# design.net
KiCad netlist of a schematic drawn in Altium Designer
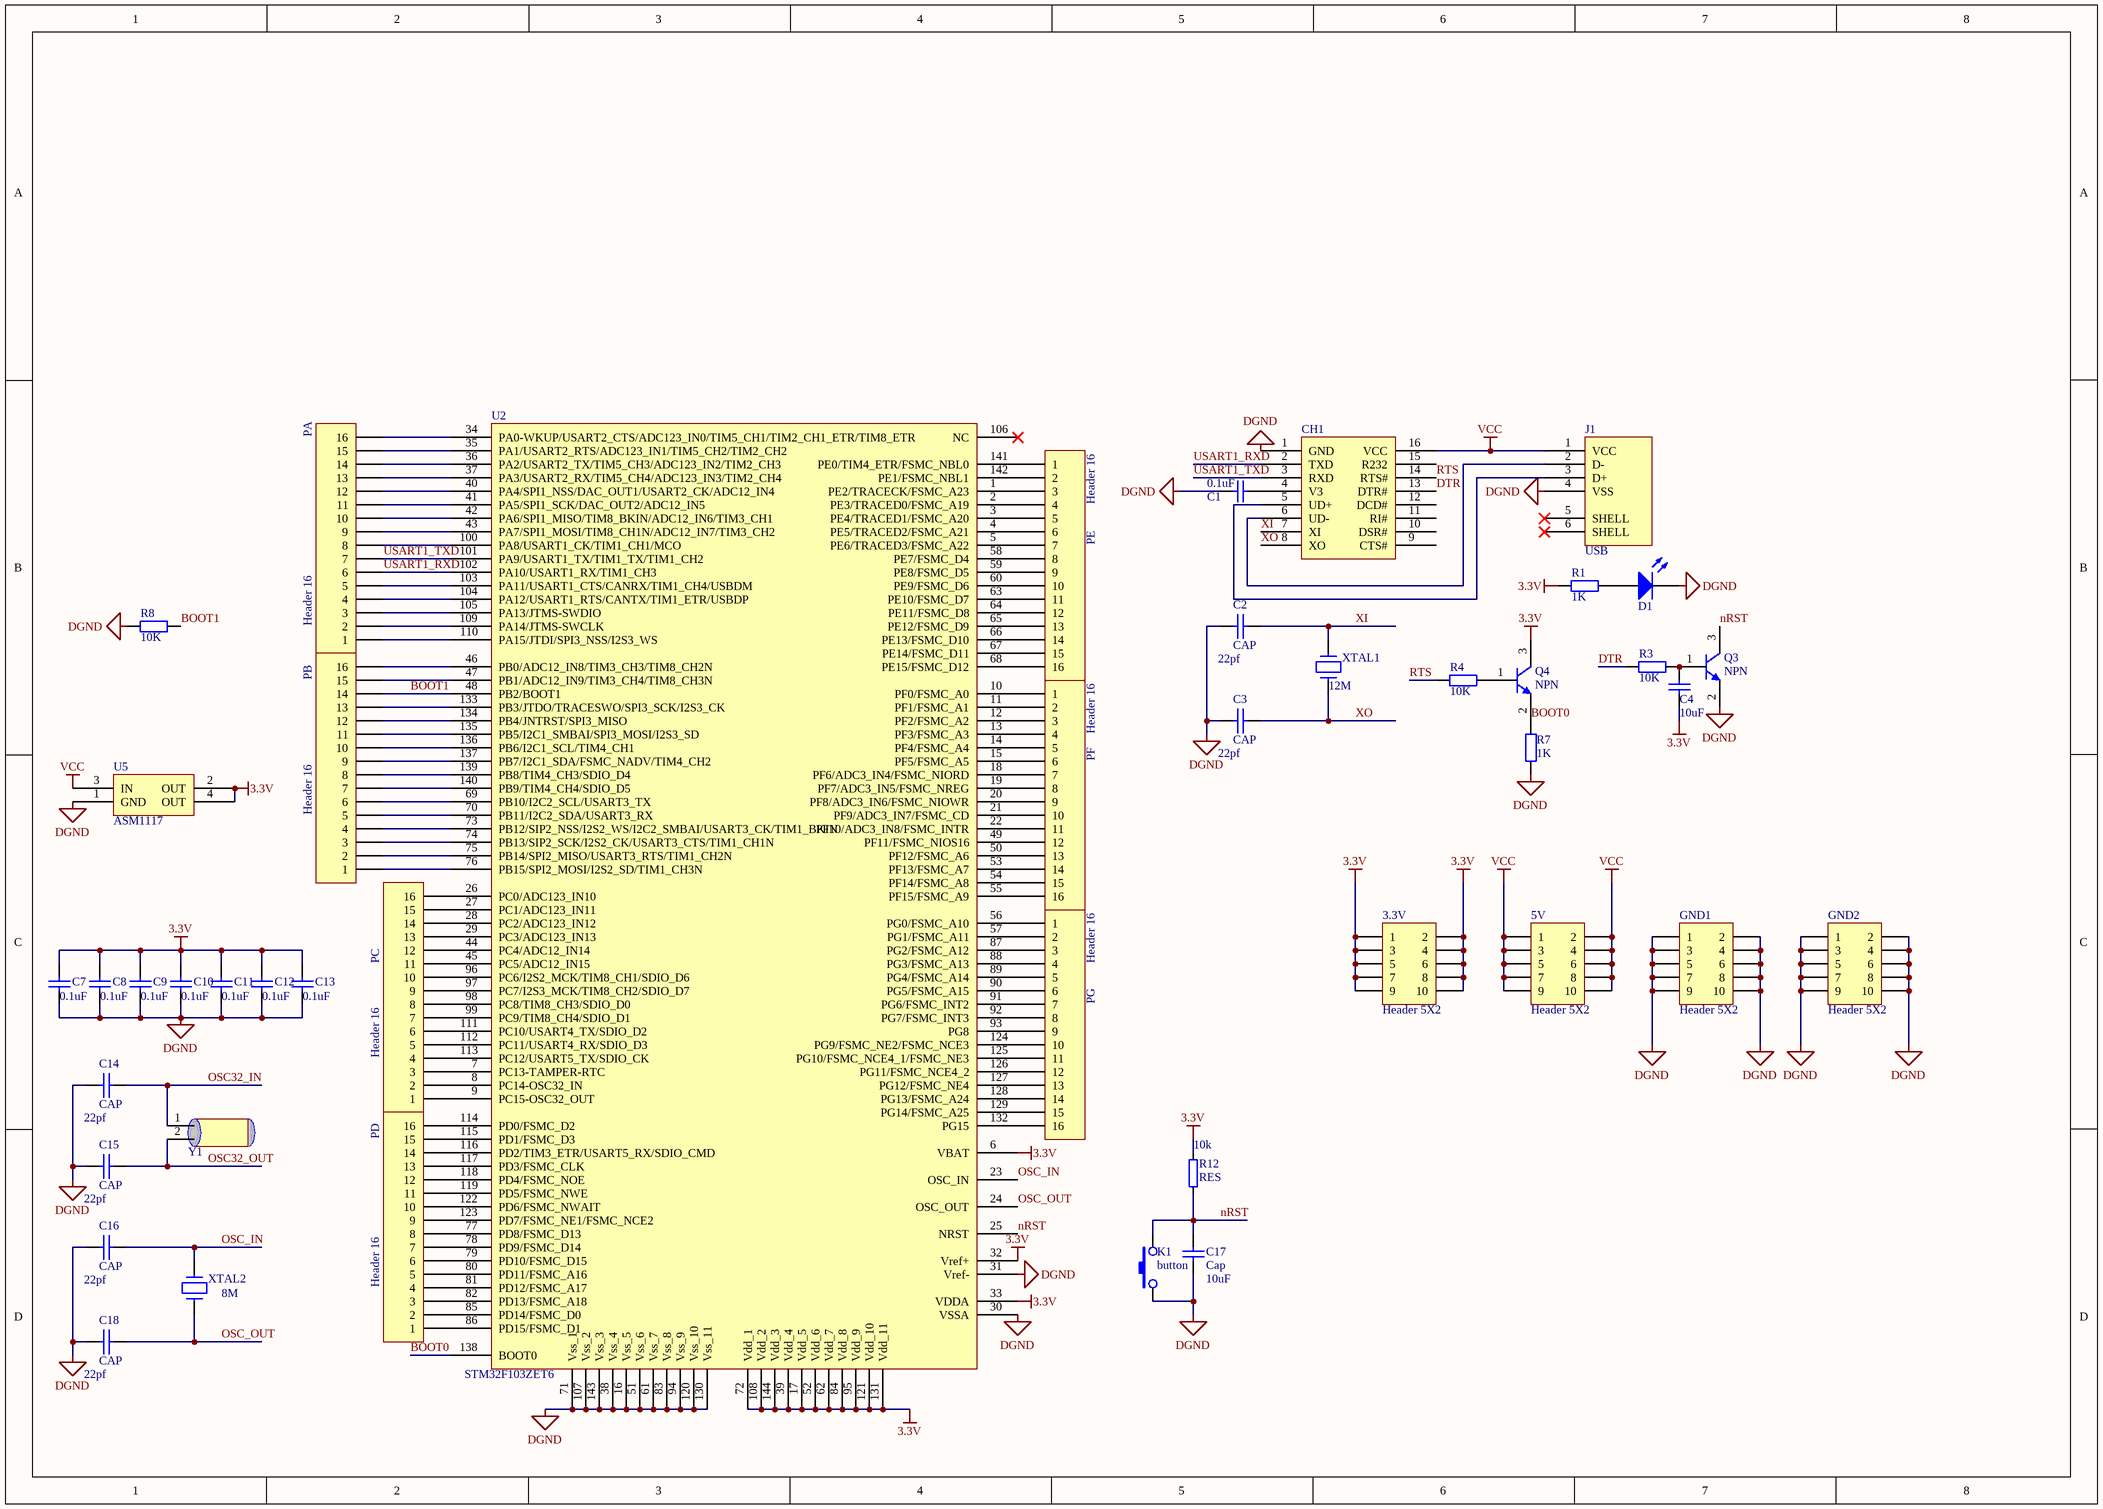
[diagram p0: 最小系统板.SchDoc]

(export (version "E")
  (design (tool "Eeschema 10.0.6"))
  (components
    (comp (ref "3.3V")
      (value "Header 5X2")
      (footprint "HDR2X5")
      (description "Header, 5-Pin, Dual row")
      (fields (field (name "PUBLISHER") "Altium Limited"))
      (libsource (lib "Miscellaneous Connectors") (part "Header 5X2"))
    )
    (comp (ref "5V")
      (value "Header 5X2")
      (footprint "HDR2X5")
      (description "Header, 5-Pin, Dual row")
      (fields (field (name "PUBLISHER") "Altium Limited"))
      (libsource (lib "Miscellaneous Connectors") (part "Header 5X2"))
    )
    (comp (ref "C1")
      (value "0.1uF")
      (footprint "0805")
      (description "Capacitor")
      (fields (field (name "Comment") "Cap") (field (name "PUBLISHER") "Altium Limited"))
      (libsource (lib "Miscellaneous Devices") (part "Cap"))
    )
    (comp (ref "C2")
      (value "CAP")
      (footprint "0805")
      (fields (field (name "ALTIUM_VALUE") "22pf"))
      (libsource (lib "常用元件库") (part "CAP"))
    )
    (comp (ref "C3")
      (value "CAP")
      (footprint "0805")
      (fields (field (name "ALTIUM_VALUE") "22pf"))
      (libsource (lib "常用元件库") (part "CAP"))
    )
    (comp (ref "C4")
      (value "10uF")
      (footprint "1206")
      (description "Capacitor")
      (fields (field (name "Comment") "Cap") (field (name "PUBLISHER") "Altium Limited"))
      (libsource (lib "Miscellaneous Devices") (part "Cap"))
    )
    (comp (ref "C7")
      (value "0.1uF")
      (footprint "0805")
      (description "Capacitor")
      (fields (field (name "Comment") "Cap") (field (name "PUBLISHER") "Altium Limited"))
      (libsource (lib "Miscellaneous Devices") (part "Cap"))
    )
    (comp (ref "C8")
      (value "0.1uF")
      (footprint "0805")
      (description "Capacitor")
      (fields (field (name "Comment") "Cap") (field (name "PUBLISHER") "Altium Limited"))
      (libsource (lib "Miscellaneous Devices") (part "Cap"))
    )
    (comp (ref "C9")
      (value "0.1uF")
      (footprint "0805")
      (description "Capacitor")
      (fields (field (name "Comment") "Cap") (field (name "PUBLISHER") "Altium Limited"))
      (libsource (lib "Miscellaneous Devices") (part "Cap"))
    )
    (comp (ref "C10")
      (value "0.1uF")
      (footprint "0805")
      (description "Capacitor")
      (fields (field (name "Comment") "Cap") (field (name "PUBLISHER") "Altium Limited"))
      (libsource (lib "Miscellaneous Devices") (part "Cap"))
    )
    (comp (ref "C11")
      (value "0.1uF")
      (footprint "0805")
      (description "Capacitor")
      (fields (field (name "Comment") "Cap") (field (name "PUBLISHER") "Altium Limited"))
      (libsource (lib "Miscellaneous Devices") (part "Cap"))
    )
    (comp (ref "C12")
      (value "0.1uF")
      (footprint "0805")
      (description "Capacitor")
      (fields (field (name "Comment") "Cap") (field (name "PUBLISHER") "Altium Limited"))
      (libsource (lib "Miscellaneous Devices") (part "Cap"))
    )
    (comp (ref "C13")
      (value "0.1uF")
      (footprint "0805")
      (description "Capacitor")
      (fields (field (name "Comment") "Cap") (field (name "PUBLISHER") "Altium Limited"))
      (libsource (lib "Miscellaneous Devices") (part "Cap"))
    )
    (comp (ref "C14")
      (value "CAP")
      (footprint "0805")
      (fields (field (name "ALTIUM_VALUE") "22pf"))
      (libsource (lib "常用元件库") (part "CAP"))
    )
    (comp (ref "C15")
      (value "CAP")
      (footprint "0805")
      (fields (field (name "ALTIUM_VALUE") "22pf"))
      (libsource (lib "常用元件库") (part "CAP"))
    )
    (comp (ref "C16")
      (value "CAP")
      (footprint "0805")
      (fields (field (name "ALTIUM_VALUE") "22pf"))
      (libsource (lib "常用元件库") (part "CAP"))
    )
    (comp (ref "C17")
      (value "Cap")
      (footprint "1206")
      (description "Capacitor")
      (fields (field (name "ALTIUM_VALUE") "10uF") (field (name "PUBLISHER") "Altium Limited"))
      (libsource (lib "Miscellaneous Devices") (part "Cap"))
    )
    (comp (ref "C18")
      (value "CAP")
      (footprint "0805")
      (fields (field (name "ALTIUM_VALUE") "22pf"))
      (libsource (lib "常用元件库") (part "CAP"))
    )
    (comp (ref "CH1")
      (value "Component_1")
      (footprint "SOIC127P600X170-16N")
      (libsource (lib "CH340G") (part "Component_1"))
    )
    (comp (ref "D1")
      (value "LED0")
      (footprint "LED-0805")
      (description "发光二极管")
      (fields (field (name "PUBLISHER") "Altium Limited"))
      (libsource (lib "fszhang") (part "LED0"))
    )
    (comp (ref "GND1")
      (value "Header 5X2")
      (footprint "HDR2X5")
      (description "Header, 5-Pin, Dual row")
      (fields (field (name "PUBLISHER") "Altium Limited"))
      (libsource (lib "Miscellaneous Connectors") (part "Header 5X2"))
    )
    (comp (ref "GND2")
      (value "Header 5X2")
      (footprint "HDR2X5")
      (description "Header, 5-Pin, Dual row")
      (fields (field (name "PUBLISHER") "Altium Limited"))
      (libsource (lib "Miscellaneous Connectors") (part "Header 5X2"))
    )
    (comp (ref "J1")
      (value "USB")
      (footprint "USB_B1")
      (description "USB接口")
      (libsource (lib "HDR_fszhang") (part "USB"))
    )
    (comp (ref "K1") (value "button") (footprint "SW_PB4_A1") (libsource (lib "my Library") (part "button")))
    (comp (ref "PA")
      (value "Header 16")
      (footprint "HDR1X16")
      (description "Header, 16-Pin")
      (fields (field (name "PUBLISHER") "Altium Limited"))
      (libsource (lib "") (part "Header 16_1"))
    )
    (comp (ref "PB")
      (value "Header 16")
      (footprint "HDR1X16")
      (description "Header, 16-Pin")
      (fields (field (name "PUBLISHER") "Altium Limited"))
      (libsource (lib "") (part "Header 16_1"))
    )
    (comp (ref "PC")
      (value "Header 16")
      (footprint "HDR1X16")
      (description "Header, 16-Pin")
      (fields (field (name "PUBLISHER") "Altium Limited"))
      (libsource (lib "") (part "Header 16_1"))
    )
    (comp (ref "PD")
      (value "Header 16")
      (footprint "HDR1X16")
      (description "Header, 16-Pin")
      (fields (field (name "PUBLISHER") "Altium Limited"))
      (libsource (lib "") (part "Header 16_1"))
    )
    (comp (ref "PE")
      (value "Header 16")
      (footprint "HDR1X16")
      (description "Header, 16-Pin")
      (fields (field (name "PUBLISHER") "Altium Limited"))
      (libsource (lib "Miscellaneous Connectors") (part "Header 16"))
    )
    (comp (ref "PF")
      (value "Header 16")
      (footprint "HDR1X16")
      (description "Header, 16-Pin")
      (fields (field (name "PUBLISHER") "Altium Limited"))
      (libsource (lib "Miscellaneous Connectors") (part "Header 16"))
    )
    (comp (ref "PG")
      (value "Header 16")
      (footprint "HDR1X16")
      (description "Header, 16-Pin")
      (fields (field (name "PUBLISHER") "Altium Limited"))
      (libsource (lib "Miscellaneous Connectors") (part "Header 16"))
    )
    (comp (ref "Q3")
      (value "NPN")
      (footprint "SOT23-3")
      (description "贴片三极管")
      (fields (field (name "PUBLISHER") "Altium Limited"))
      (libsource (lib "fszhang") (part "NPN1"))
    )
    (comp (ref "Q4")
      (value "NPN")
      (footprint "SOT23-3")
      (description "贴片三极管")
      (fields (field (name "PUBLISHER") "Altium Limited"))
      (libsource (lib "fszhang") (part "NPN1"))
    )
    (comp (ref "R1")
      (value "1K")
      (footprint "0805")
      (description "Resistor")
      (fields (field (name "Comment") "Res2") (field (name "PUBLISHER") "Altium Limited"))
      (libsource (lib "") (part "Res2_1"))
    )
    (comp (ref "R3")
      (value "10K")
      (footprint "0805")
      (description "Resistor")
      (fields (field (name "Comment") "Res2") (field (name "PUBLISHER") "Altium Limited"))
      (libsource (lib "Miscellaneous Devices") (part "Res2"))
    )
    (comp (ref "R4")
      (value "10K")
      (footprint "0805")
      (description "Resistor")
      (fields (field (name "Comment") "Res2") (field (name "PUBLISHER") "Altium Limited"))
      (libsource (lib "Miscellaneous Devices") (part "Res2"))
    )
    (comp (ref "R7")
      (value "1K")
      (footprint "0805")
      (description "Resistor")
      (fields (field (name "Comment") "Res2") (field (name "PUBLISHER") "Altium Limited"))
      (libsource (lib "") (part "Res2_2"))
    )
    (comp (ref "R8")
      (value "10K")
      (footprint "0805")
      (description "Resistor")
      (fields (field (name "Comment") "Res2") (field (name "PUBLISHER") "Altium Limited"))
      (libsource (lib "") (part "Res2_1"))
    )
    (comp (ref "R12")
      (value "RES")
      (footprint "0805")
      (fields (field (name "ALTIUM_VALUE") "10k"))
      (libsource (lib "电阻") (part "RES"))
    )
    (comp (ref "U2")
      (value "STM32F103ZET6")
      (footprint "TQFP-144")
      (libsource (lib "STM32F103ZET6") (part "STM32F103ZET6"))
    )
    (comp (ref "U5")
      (value "ASM1117")
      (footprint "SOT223")
      (description "3.3V稳压芯片")
      (libsource (lib "fszhang") (part "ASM1117"))
    )
    (comp (ref "XTAL1")
      (value "12M")
      (footprint "X-SM49")
      (fields (field (name "Comment") "CRYSTAL"))
      (libsource (lib "常用元件库") (part "CRYSTAL"))
    )
    (comp (ref "XTAL2")
      (value "8M")
      (footprint "X-SM49")
      (fields (field (name "Comment") "CRYSTAL"))
      (libsource (lib "常用元件库") (part "CRYSTAL"))
    )
    (comp (ref "Y1") (value "32K晶振") (footprint "X-TC15") (libsource (lib "Library 1") (part "32K晶振")))
  )
  (nets
    (net (code "1") (name "/BOOT0") (class "Default")
      (node (ref "Q4") (pin "2") (pinfunction "E_2") (pintype "passive"))
      (node (ref "R7") (pin "2") (pinfunction "2_2") (pintype "passive"))
      (node (ref "U2") (pin "138") (pinfunction "BOOT0_138") (pintype "passive"))
    )
    (net (code "2") (name "/BOOT1") (class "Default")
      (node (ref "PB") (pin "14") (pinfunction "14_14") (pintype "passive"))
      (node (ref "R8") (pin "2") (pinfunction "2_2") (pintype "passive"))
      (node (ref "U2") (pin "48") (pinfunction "PB2/BOOT1_48") (pintype "passive"))
    )
    (net (code "3") (name "/DTR") (class "Default")
      (node (ref "CH1") (pin "13") (pinfunction "DTR#_13") (pintype "passive"))
      (node (ref "R3") (pin "2") (pinfunction "2_2") (pintype "passive"))
    )
    (net (code "4") (name "/OSC32_IN") (class "Default")
      (node (ref "C14") (pin "2") (pinfunction "2_2") (pintype "passive"))
      (node (ref "Y1") (pin "1") (pinfunction "X1_1") (pintype "passive"))
    )
    (net (code "5") (name "/OSC32_OUT") (class "Default")
      (node (ref "C15") (pin "2") (pinfunction "2_2") (pintype "passive"))
      (node (ref "Y1") (pin "2") (pinfunction "X2_2") (pintype "passive"))
    )
    (net (code "6") (name "/OSC_IN") (class "Default")
      (node (ref "C16") (pin "2") (pinfunction "2_2") (pintype "passive"))
      (node (ref "U2") (pin "23") (pinfunction "OSC_IN_23") (pintype "passive"))
      (node (ref "XTAL2") (pin "2") (pinfunction "2_2") (pintype "passive"))
    )
    (net (code "7") (name "/OSC_OUT") (class "Default")
      (node (ref "C18") (pin "2") (pinfunction "2_2") (pintype "passive"))
      (node (ref "U2") (pin "24") (pinfunction "OSC_OUT_24") (pintype "passive"))
      (node (ref "XTAL2") (pin "1") (pinfunction "1_1") (pintype "passive"))
    )
    (net (code "8") (name "/RTS") (class "Default")
      (node (ref "CH1") (pin "14") (pinfunction "RTS#_14") (pintype "passive"))
      (node (ref "R4") (pin "2") (pinfunction "2_2") (pintype "passive"))
    )
    (net (code "9") (name "/USART1_RXD") (class "Default")
      (node (ref "CH1") (pin "2") (pinfunction "TXD_2") (pintype "passive"))
      (node (ref "PA") (pin "6") (pinfunction "6_6") (pintype "passive"))
      (node (ref "U2") (pin "102") (pinfunction "PA10/USART1_RX/TIM1_CH3_102") (pintype "passive"))
    )
    (net (code "10") (name "/USART1_TXD") (class "Default")
      (node (ref "CH1") (pin "3") (pinfunction "RXD_3") (pintype "passive"))
      (node (ref "PA") (pin "7") (pinfunction "7_7") (pintype "passive"))
      (node (ref "U2") (pin "101") (pinfunction "PA9/USART1_TX/TIM1_TX/TIM1_CH2_101") (pintype "passive"))
    )
    (net (code "11") (name "/XI") (class "Default")
      (node (ref "C2") (pin "2") (pinfunction "2_2") (pintype "passive"))
      (node (ref "CH1") (pin "7") (pinfunction "XI_7") (pintype "passive"))
      (node (ref "XTAL1") (pin "2") (pinfunction "2_2") (pintype "passive"))
    )
    (net (code "12") (name "/XO") (class "Default")
      (node (ref "C3") (pin "2") (pinfunction "2_2") (pintype "passive"))
      (node (ref "CH1") (pin "8") (pinfunction "XO_8") (pintype "passive"))
      (node (ref "XTAL1") (pin "1") (pinfunction "1_1") (pintype "passive"))
    )
    (net (code "13") (name "/nRST") (class "Default")
      (node (ref "C17") (pin "2") (pinfunction "2_2") (pintype "passive"))
      (node (ref "K1") (pin "2") (pinfunction "2_2") (pintype "passive"))
      (node (ref "Q3") (pin "3") (pinfunction "C_3") (pintype "passive"))
      (node (ref "R12") (pin "1") (pinfunction "1_1") (pintype "passive"))
      (node (ref "U2") (pin "25") (pinfunction "NRST_25") (pintype "passive"))
    )
    (net (code "14") (name "3.3V") (class "Default")
      (node (ref "3.3V") (pin "1") (pinfunction "1_1") (pintype "passive"))
      (node (ref "3.3V") (pin "10") (pinfunction "10_10") (pintype "passive"))
      (node (ref "3.3V") (pin "2") (pinfunction "2_2") (pintype "passive"))
      (node (ref "3.3V") (pin "3") (pinfunction "3_3") (pintype "passive"))
      (node (ref "3.3V") (pin "4") (pinfunction "4_4") (pintype "passive"))
      (node (ref "3.3V") (pin "5") (pinfunction "5_5") (pintype "passive"))
      (node (ref "3.3V") (pin "6") (pinfunction "6_6") (pintype "passive"))
      (node (ref "3.3V") (pin "7") (pinfunction "7_7") (pintype "passive"))
      (node (ref "3.3V") (pin "8") (pinfunction "8_8") (pintype "passive"))
      (node (ref "3.3V") (pin "9") (pinfunction "9_9") (pintype "passive"))
      (node (ref "C10") (pin "2") (pinfunction "2_2") (pintype "passive"))
      (node (ref "C11") (pin "2") (pinfunction "2_2") (pintype "passive"))
      (node (ref "C12") (pin "2") (pinfunction "2_2") (pintype "passive"))
      (node (ref "C13") (pin "2") (pinfunction "2_2") (pintype "passive"))
      (node (ref "C4") (pin "1") (pinfunction "1_1") (pintype "passive"))
      (node (ref "C7") (pin "2") (pinfunction "2_2") (pintype "passive"))
      (node (ref "C8") (pin "2") (pinfunction "2_2") (pintype "passive"))
      (node (ref "C9") (pin "2") (pinfunction "2_2") (pintype "passive"))
      (node (ref "Q4") (pin "3") (pinfunction "C_3") (pintype "passive"))
      (node (ref "R1") (pin "1") (pinfunction "1_1") (pintype "passive"))
      (node (ref "R12") (pin "2") (pinfunction "2_2") (pintype "passive"))
      (node (ref "U2") (pin "108") (pinfunction "Vdd_2_108") (pintype "passive"))
      (node (ref "U2") (pin "121") (pinfunction "Vdd_10_121") (pintype "passive"))
      (node (ref "U2") (pin "131") (pinfunction "Vdd_11_131") (pintype "passive"))
      (node (ref "U2") (pin "144") (pinfunction "Vdd_3_144") (pintype "passive"))
      (node (ref "U2") (pin "17") (pinfunction "Vdd_5_17") (pintype "passive"))
      (node (ref "U2") (pin "32") (pinfunction "Vref+_32") (pintype "passive"))
      (node (ref "U2") (pin "33") (pinfunction "VDDA_33") (pintype "passive"))
      (node (ref "U2") (pin "39") (pinfunction "Vdd_4_39") (pintype "passive"))
      (node (ref "U2") (pin "52") (pinfunction "Vdd_6_52") (pintype "passive"))
      (node (ref "U2") (pin "6") (pinfunction "VBAT_6") (pintype "passive"))
      (node (ref "U2") (pin "62") (pinfunction "Vdd_7_62") (pintype "passive"))
      (node (ref "U2") (pin "72") (pinfunction "Vdd_1_72") (pintype "passive"))
      (node (ref "U2") (pin "84") (pinfunction "Vdd_8_84") (pintype "passive"))
      (node (ref "U2") (pin "95") (pinfunction "Vdd_9_95") (pintype "passive"))
      (node (ref "U5") (pin "2") (pinfunction "OUT_2") (pintype "passive"))
      (node (ref "U5") (pin "4") (pinfunction "OUT_4") (pintype "passive"))
    )
    (net (code "15") (name "DGND") (class "Default")
      (node (ref "C1") (pin "2") (pinfunction "2_2") (pintype "passive"))
      (node (ref "C10") (pin "1") (pinfunction "1_1") (pintype "passive"))
      (node (ref "C11") (pin "1") (pinfunction "1_1") (pintype "passive"))
      (node (ref "C12") (pin "1") (pinfunction "1_1") (pintype "passive"))
      (node (ref "C13") (pin "1") (pinfunction "1_1") (pintype "passive"))
      (node (ref "C14") (pin "1") (pinfunction "1_1") (pintype "passive"))
      (node (ref "C15") (pin "1") (pinfunction "1_1") (pintype "passive"))
      (node (ref "C16") (pin "1") (pinfunction "1_1") (pintype "passive"))
      (node (ref "C17") (pin "1") (pinfunction "1_1") (pintype "passive"))
      (node (ref "C18") (pin "1") (pinfunction "1_1") (pintype "passive"))
      (node (ref "C2") (pin "1") (pinfunction "1_1") (pintype "passive"))
      (node (ref "C3") (pin "1") (pinfunction "1_1") (pintype "passive"))
      (node (ref "C7") (pin "1") (pinfunction "1_1") (pintype "passive"))
      (node (ref "C8") (pin "1") (pinfunction "1_1") (pintype "passive"))
      (node (ref "C9") (pin "1") (pinfunction "1_1") (pintype "passive"))
      (node (ref "CH1") (pin "1") (pinfunction "GND_1") (pintype "passive"))
      (node (ref "D1") (pin "2") (pinfunction "K_2") (pintype "passive"))
      (node (ref "GND1") (pin "1") (pinfunction "1_1") (pintype "passive"))
      (node (ref "GND1") (pin "10") (pinfunction "10_10") (pintype "passive"))
      (node (ref "GND1") (pin "2") (pinfunction "2_2") (pintype "passive"))
      (node (ref "GND1") (pin "3") (pinfunction "3_3") (pintype "passive"))
      (node (ref "GND1") (pin "4") (pinfunction "4_4") (pintype "passive"))
      (node (ref "GND1") (pin "5") (pinfunction "5_5") (pintype "passive"))
      (node (ref "GND1") (pin "6") (pinfunction "6_6") (pintype "passive"))
      (node (ref "GND1") (pin "7") (pinfunction "7_7") (pintype "passive"))
      (node (ref "GND1") (pin "8") (pinfunction "8_8") (pintype "passive"))
      (node (ref "GND1") (pin "9") (pinfunction "9_9") (pintype "passive"))
      (node (ref "GND2") (pin "1") (pinfunction "1_1") (pintype "passive"))
      (node (ref "GND2") (pin "10") (pinfunction "10_10") (pintype "passive"))
      (node (ref "GND2") (pin "2") (pinfunction "2_2") (pintype "passive"))
      (node (ref "GND2") (pin "3") (pinfunction "3_3") (pintype "passive"))
      (node (ref "GND2") (pin "4") (pinfunction "4_4") (pintype "passive"))
      (node (ref "GND2") (pin "5") (pinfunction "5_5") (pintype "passive"))
      (node (ref "GND2") (pin "6") (pinfunction "6_6") (pintype "passive"))
      (node (ref "GND2") (pin "7") (pinfunction "7_7") (pintype "passive"))
      (node (ref "GND2") (pin "8") (pinfunction "8_8") (pintype "passive"))
      (node (ref "GND2") (pin "9") (pinfunction "9_9") (pintype "passive"))
      (node (ref "J1") (pin "4") (pinfunction "VSS_4") (pintype "passive"))
      (node (ref "K1") (pin "1") (pinfunction "1_1") (pintype "passive"))
      (node (ref "Q3") (pin "2") (pinfunction "E_2") (pintype "passive"))
      (node (ref "R7") (pin "1") (pinfunction "1_1") (pintype "passive"))
      (node (ref "R8") (pin "1") (pinfunction "1_1") (pintype "passive"))
      (node (ref "U2") (pin "107") (pinfunction "Vss_2_107") (pintype "passive"))
      (node (ref "U2") (pin "120") (pinfunction "Vss_10_120") (pintype "passive"))
      (node (ref "U2") (pin "130") (pinfunction "Vss_11_130") (pintype "passive"))
      (node (ref "U2") (pin "143") (pinfunction "Vss_3_143") (pintype "passive"))
      (node (ref "U2") (pin "16") (pinfunction "Vss_5_16") (pintype "passive"))
      (node (ref "U2") (pin "30") (pinfunction "VSSA_30") (pintype "passive"))
      (node (ref "U2") (pin "31") (pinfunction "Vref-_31") (pintype "passive"))
      (node (ref "U2") (pin "38") (pinfunction "Vss_4_38") (pintype "passive"))
      (node (ref "U2") (pin "51") (pinfunction "Vss_6_51") (pintype "passive"))
      (node (ref "U2") (pin "61") (pinfunction "Vss_7_61") (pintype "passive"))
      (node (ref "U2") (pin "71") (pinfunction "Vss_1_71") (pintype "passive"))
      (node (ref "U2") (pin "83") (pinfunction "Vss_8_83") (pintype "passive"))
      (node (ref "U2") (pin "94") (pinfunction "Vss_9_94") (pintype "passive"))
      (node (ref "U5") (pin "1") (pinfunction "GND_1") (pintype "passive"))
    )
    (net (code "16") (name "Net-(CH1-UD+)") (class "Default")
      (node (ref "CH1") (pin "5") (pinfunction "UD+_5") (pintype "passive"))
      (node (ref "J1") (pin "3") (pinfunction "D+_3") (pintype "passive"))
    )
    (net (code "17") (name "Net-(CH1-UD-)") (class "Default")
      (node (ref "CH1") (pin "6") (pinfunction "UD-_6") (pintype "passive"))
      (node (ref "J1") (pin "2") (pinfunction "D-_2") (pintype "passive"))
    )
    (net (code "18") (name "Net-(CH1-V3)") (class "Default")
      (node (ref "C1") (pin "1") (pinfunction "1_1") (pintype "passive"))
      (node (ref "CH1") (pin "4") (pinfunction "V3_4") (pintype "passive"))
    )
    (net (code "19") (name "Net-(D1-A)") (class "Default")
      (node (ref "D1") (pin "1") (pinfunction "A_1") (pintype "passive"))
      (node (ref "R1") (pin "2") (pinfunction "2_2") (pintype "passive"))
    )
    (net (code "20") (name "Net-(Q3-B)") (class "Default")
      (node (ref "C4") (pin "2") (pinfunction "2_2") (pintype "passive"))
      (node (ref "Q3") (pin "1") (pinfunction "B_1") (pintype "passive"))
      (node (ref "R3") (pin "1") (pinfunction "1_1") (pintype "passive"))
    )
    (net (code "21") (name "Net-(Q4-B)") (class "Default")
      (node (ref "Q4") (pin "1") (pinfunction "B_1") (pintype "passive"))
      (node (ref "R4") (pin "1") (pinfunction "1_1") (pintype "passive"))
    )
    (net (code "22") (name "Net-(U2-PA0-WKUP{slash}USART2_CTS{slash}ADC123_IN0{slash}TIM5_CH1{slash}TIM2_CH1_ETR{slash}TIM8_ETR)") (class "Default")
      (node (ref "PA") (pin "16") (pinfunction "16_16") (pintype "passive"))
      (node (ref "U2") (pin "34") (pinfunction "PA0-WKUP/USART2_CTS/ADC123_IN0/TIM5_CH1/TIM2_CH1_ETR/TIM8_ETR_34") (pintype "passive"))
    )
    (net (code "23") (name "Net-(U2-PA1{slash}USART2_RTS{slash}ADC123_IN1{slash}TIM5_CH2{slash}TIM2_CH2)") (class "Default")
      (node (ref "PA") (pin "15") (pinfunction "15_15") (pintype "passive"))
      (node (ref "U2") (pin "35") (pinfunction "PA1/USART2_RTS/ADC123_IN1/TIM5_CH2/TIM2_CH2_35") (pintype "passive"))
    )
    (net (code "24") (name "Net-(U2-PA2{slash}USART2_TX{slash}TIM5_CH3{slash}ADC123_IN2{slash}TIM2_CH3)") (class "Default")
      (node (ref "PA") (pin "14") (pinfunction "14_14") (pintype "passive"))
      (node (ref "U2") (pin "36") (pinfunction "PA2/USART2_TX/TIM5_CH3/ADC123_IN2/TIM2_CH3_36") (pintype "passive"))
    )
    (net (code "25") (name "Net-(U2-PA3{slash}USART2_RX{slash}TIM5_CH4{slash}ADC123_IN3{slash}TIM2_CH4)") (class "Default")
      (node (ref "PA") (pin "13") (pinfunction "13_13") (pintype "passive"))
      (node (ref "U2") (pin "37") (pinfunction "PA3/USART2_RX/TIM5_CH4/ADC123_IN3/TIM2_CH4_37") (pintype "passive"))
    )
    (net (code "26") (name "Net-(U2-PA4{slash}SPI1_NSS{slash}DAC_OUT1{slash}USART2_CK{slash}ADC12_IN4)") (class "Default")
      (node (ref "PA") (pin "12") (pinfunction "12_12") (pintype "passive"))
      (node (ref "U2") (pin "40") (pinfunction "PA4/SPI1_NSS/DAC_OUT1/USART2_CK/ADC12_IN4_40") (pintype "passive"))
    )
    (net (code "27") (name "Net-(U2-PA5{slash}SPI1_SCK{slash}DAC_OUT2{slash}ADC12_IN5)") (class "Default")
      (node (ref "PA") (pin "11") (pinfunction "11_11") (pintype "passive"))
      (node (ref "U2") (pin "41") (pinfunction "PA5/SPI1_SCK/DAC_OUT2/ADC12_IN5_41") (pintype "passive"))
    )
    (net (code "28") (name "Net-(U2-PA6{slash}SPI1_MISO{slash}TIM8_BKIN{slash}ADC12_IN6{slash}TIM3_CH1)") (class "Default")
      (node (ref "PA") (pin "10") (pinfunction "10_10") (pintype "passive"))
      (node (ref "U2") (pin "42") (pinfunction "PA6/SPI1_MISO/TIM8_BKIN/ADC12_IN6/TIM3_CH1_42") (pintype "passive"))
    )
    (net (code "29") (name "Net-(U2-PA7{slash}SPI1_MOSI{slash}TIM8_CH1N{slash}ADC12_IN7{slash}TIM3_CH2)") (class "Default")
      (node (ref "PA") (pin "9") (pinfunction "9_9") (pintype "passive"))
      (node (ref "U2") (pin "43") (pinfunction "PA7/SPI1_MOSI/TIM8_CH1N/ADC12_IN7/TIM3_CH2_43") (pintype "passive"))
    )
    (net (code "30") (name "Net-(U2-PA8{slash}USART1_CK{slash}TIM1_CH1{slash}MCO)") (class "Default")
      (node (ref "PA") (pin "8") (pinfunction "8_8") (pintype "passive"))
      (node (ref "U2") (pin "100") (pinfunction "PA8/USART1_CK/TIM1_CH1/MCO_100") (pintype "passive"))
    )
    (net (code "31") (name "Net-(U2-PA11{slash}USART1_CTS{slash}CANRX{slash}TIM1_CH4{slash}USBDM)") (class "Default")
      (node (ref "PA") (pin "5") (pinfunction "5_5") (pintype "passive"))
      (node (ref "U2") (pin "103") (pinfunction "PA11/USART1_CTS/CANRX/TIM1_CH4/USBDM_103") (pintype "passive"))
    )
    (net (code "32") (name "Net-(U2-PA12{slash}USART1_RTS{slash}CANTX{slash}TIM1_ETR{slash}USBDP)") (class "Default")
      (node (ref "PA") (pin "4") (pinfunction "4_4") (pintype "passive"))
      (node (ref "U2") (pin "104") (pinfunction "PA12/USART1_RTS/CANTX/TIM1_ETR/USBDP_104") (pintype "passive"))
    )
    (net (code "33") (name "Net-(U2-PA13{slash}JTMS-SWDIO)") (class "Default")
      (node (ref "PA") (pin "3") (pinfunction "3_3") (pintype "passive"))
      (node (ref "U2") (pin "105") (pinfunction "PA13/JTMS-SWDIO_105") (pintype "passive"))
    )
    (net (code "34") (name "Net-(U2-PA14{slash}JTMS-SWCLK)") (class "Default")
      (node (ref "PA") (pin "2") (pinfunction "2_2") (pintype "passive"))
      (node (ref "U2") (pin "109") (pinfunction "PA14/JTMS-SWCLK_109") (pintype "passive"))
    )
    (net (code "35") (name "Net-(U2-PA15{slash}JTDI{slash}SPI3_NSS{slash}I2S3_WS)") (class "Default")
      (node (ref "PA") (pin "1") (pinfunction "1_1") (pintype "passive"))
      (node (ref "U2") (pin "110") (pinfunction "PA15/JTDI/SPI3_NSS/I2S3_WS_110") (pintype "passive"))
    )
    (net (code "36") (name "Net-(U2-PB0{slash}ADC12_IN8{slash}TIM3_CH3{slash}TIM8_CH2N)") (class "Default")
      (node (ref "PB") (pin "16") (pinfunction "16_16") (pintype "passive"))
      (node (ref "U2") (pin "46") (pinfunction "PB0/ADC12_IN8/TIM3_CH3/TIM8_CH2N_46") (pintype "passive"))
    )
    (net (code "37") (name "Net-(U2-PB1{slash}ADC12_IN9{slash}TIM3_CH4{slash}TIM8_CH3N)") (class "Default")
      (node (ref "PB") (pin "15") (pinfunction "15_15") (pintype "passive"))
      (node (ref "U2") (pin "47") (pinfunction "PB1/ADC12_IN9/TIM3_CH4/TIM8_CH3N_47") (pintype "passive"))
    )
    (net (code "38") (name "Net-(U2-PB3{slash}JTDO{slash}TRACESWO{slash}SPI3_SCK{slash}I2S3_CK)") (class "Default")
      (node (ref "PB") (pin "13") (pinfunction "13_13") (pintype "passive"))
      (node (ref "U2") (pin "133") (pinfunction "PB3/JTDO/TRACESWO/SPI3_SCK/I2S3_CK_133") (pintype "passive"))
    )
    (net (code "39") (name "Net-(U2-PB4{slash}JNTRST{slash}SPI3_MISO)") (class "Default")
      (node (ref "PB") (pin "12") (pinfunction "12_12") (pintype "passive"))
      (node (ref "U2") (pin "134") (pinfunction "PB4/JNTRST/SPI3_MISO_134") (pintype "passive"))
    )
    (net (code "40") (name "Net-(U2-PB5{slash}I2C1_SMBAI{slash}SPI3_MOSI{slash}I2S3_SD)") (class "Default")
      (node (ref "PB") (pin "11") (pinfunction "11_11") (pintype "passive"))
      (node (ref "U2") (pin "135") (pinfunction "PB5/I2C1_SMBAI/SPI3_MOSI/I2S3_SD_135") (pintype "passive"))
    )
    (net (code "41") (name "Net-(U2-PB6{slash}I2C1_SCL{slash}TIM4_CH1)") (class "Default")
      (node (ref "PB") (pin "10") (pinfunction "10_10") (pintype "passive"))
      (node (ref "U2") (pin "136") (pinfunction "PB6/I2C1_SCL/TIM4_CH1_136") (pintype "passive"))
    )
    (net (code "42") (name "Net-(U2-PB7{slash}I2C1_SDA{slash}FSMC_NADV{slash}TIM4_CH2)") (class "Default")
      (node (ref "PB") (pin "9") (pinfunction "9_9") (pintype "passive"))
      (node (ref "U2") (pin "137") (pinfunction "PB7/I2C1_SDA/FSMC_NADV/TIM4_CH2_137") (pintype "passive"))
    )
    (net (code "43") (name "Net-(U2-PB8{slash}TIM4_CH3{slash}SDIO_D4)") (class "Default")
      (node (ref "PB") (pin "8") (pinfunction "8_8") (pintype "passive"))
      (node (ref "U2") (pin "139") (pinfunction "PB8/TIM4_CH3/SDIO_D4_139") (pintype "passive"))
    )
    (net (code "44") (name "Net-(U2-PB9{slash}TIM4_CH4{slash}SDIO_D5)") (class "Default")
      (node (ref "PB") (pin "7") (pinfunction "7_7") (pintype "passive"))
      (node (ref "U2") (pin "140") (pinfunction "PB9/TIM4_CH4/SDIO_D5_140") (pintype "passive"))
    )
    (net (code "45") (name "Net-(U2-PB10{slash}I2C2_SCL{slash}USART3_TX)") (class "Default")
      (node (ref "PB") (pin "6") (pinfunction "6_6") (pintype "passive"))
      (node (ref "U2") (pin "69") (pinfunction "PB10/I2C2_SCL/USART3_TX_69") (pintype "passive"))
    )
    (net (code "46") (name "Net-(U2-PB11{slash}I2C2_SDA{slash}USART3_RX)") (class "Default")
      (node (ref "PB") (pin "5") (pinfunction "5_5") (pintype "passive"))
      (node (ref "U2") (pin "70") (pinfunction "PB11/I2C2_SDA/USART3_RX_70") (pintype "passive"))
    )
    (net (code "47") (name "Net-(U2-PB12{slash}SIP2_NSS{slash}I2S2_WS{slash}I2C2_SMBAI{slash}USART3_CK{slash}TIM1_BKIN)") (class "Default")
      (node (ref "PB") (pin "4") (pinfunction "4_4") (pintype "passive"))
      (node (ref "U2") (pin "73") (pinfunction "PB12/SIP2_NSS/I2S2_WS/I2C2_SMBAI/USART3_CK/TIM1_BKIN_73") (pintype "passive"))
    )
    (net (code "48") (name "Net-(U2-PB13{slash}SIP2_SCK{slash}I2S2_CK{slash}USART3_CTS{slash}TIM1_CH1N)") (class "Default")
      (node (ref "PB") (pin "3") (pinfunction "3_3") (pintype "passive"))
      (node (ref "U2") (pin "74") (pinfunction "PB13/SIP2_SCK/I2S2_CK/USART3_CTS/TIM1_CH1N_74") (pintype "passive"))
    )
    (net (code "49") (name "Net-(U2-PB14{slash}SPI2_MISO{slash}USART3_RTS{slash}TIM1_CH2N)") (class "Default")
      (node (ref "PB") (pin "2") (pinfunction "2_2") (pintype "passive"))
      (node (ref "U2") (pin "75") (pinfunction "PB14/SPI2_MISO/USART3_RTS/TIM1_CH2N_75") (pintype "passive"))
    )
    (net (code "50") (name "Net-(U2-PB15{slash}SPI2_MOSI{slash}I2S2_SD{slash}TIM1_CH3N)") (class "Default")
      (node (ref "PB") (pin "1") (pinfunction "1_1") (pintype "passive"))
      (node (ref "U2") (pin "76") (pinfunction "PB15/SPI2_MOSI/I2S2_SD/TIM1_CH3N_76") (pintype "passive"))
    )
    (net (code "51") (name "Net-(U2-PC0{slash}ADC123_IN10)") (class "Default")
      (node (ref "PC") (pin "16") (pinfunction "16_16") (pintype "passive"))
      (node (ref "U2") (pin "26") (pinfunction "PC0/ADC123_IN10_26") (pintype "passive"))
    )
    (net (code "52") (name "Net-(U2-PC1{slash}ADC123_IN11)") (class "Default")
      (node (ref "PC") (pin "15") (pinfunction "15_15") (pintype "passive"))
      (node (ref "U2") (pin "27") (pinfunction "PC1/ADC123_IN11_27") (pintype "passive"))
    )
    (net (code "53") (name "Net-(U2-PC2{slash}ADC123_IN12)") (class "Default")
      (node (ref "PC") (pin "14") (pinfunction "14_14") (pintype "passive"))
      (node (ref "U2") (pin "28") (pinfunction "PC2/ADC123_IN12_28") (pintype "passive"))
    )
    (net (code "54") (name "Net-(U2-PC3{slash}ADC123_IN13)") (class "Default")
      (node (ref "PC") (pin "13") (pinfunction "13_13") (pintype "passive"))
      (node (ref "U2") (pin "29") (pinfunction "PC3/ADC123_IN13_29") (pintype "passive"))
    )
    (net (code "55") (name "Net-(U2-PC4{slash}ADC12_IN14)") (class "Default")
      (node (ref "PC") (pin "12") (pinfunction "12_12") (pintype "passive"))
      (node (ref "U2") (pin "44") (pinfunction "PC4/ADC12_IN14_44") (pintype "passive"))
    )
    (net (code "56") (name "Net-(U2-PC5{slash}ADC12_IN15)") (class "Default")
      (node (ref "PC") (pin "11") (pinfunction "11_11") (pintype "passive"))
      (node (ref "U2") (pin "45") (pinfunction "PC5/ADC12_IN15_45") (pintype "passive"))
    )
    (net (code "57") (name "Net-(U2-PC6{slash}I2S2_MCK{slash}TIM8_CH1{slash}SDIO_D6)") (class "Default")
      (node (ref "PC") (pin "10") (pinfunction "10_10") (pintype "passive"))
      (node (ref "U2") (pin "96") (pinfunction "PC6/I2S2_MCK/TIM8_CH1/SDIO_D6_96") (pintype "passive"))
    )
    (net (code "58") (name "Net-(U2-PC7{slash}I2S3_MCK{slash}TIM8_CH2{slash}SDIO_D7)") (class "Default")
      (node (ref "PC") (pin "9") (pinfunction "9_9") (pintype "passive"))
      (node (ref "U2") (pin "97") (pinfunction "PC7/I2S3_MCK/TIM8_CH2/SDIO_D7_97") (pintype "passive"))
    )
    (net (code "59") (name "Net-(U2-PC8{slash}TIM8_CH3{slash}SDIO_D0)") (class "Default")
      (node (ref "PC") (pin "8") (pinfunction "8_8") (pintype "passive"))
      (node (ref "U2") (pin "98") (pinfunction "PC8/TIM8_CH3/SDIO_D0_98") (pintype "passive"))
    )
    (net (code "60") (name "Net-(U2-PC9{slash}TIM8_CH4{slash}SDIO_D1)") (class "Default")
      (node (ref "PC") (pin "7") (pinfunction "7_7") (pintype "passive"))
      (node (ref "U2") (pin "99") (pinfunction "PC9/TIM8_CH4/SDIO_D1_99") (pintype "passive"))
    )
    (net (code "61") (name "Net-(U2-PC10{slash}USART4_TX{slash}SDIO_D2)") (class "Default")
      (node (ref "PC") (pin "6") (pinfunction "6_6") (pintype "passive"))
      (node (ref "U2") (pin "111") (pinfunction "PC10/USART4_TX/SDIO_D2_111") (pintype "passive"))
    )
    (net (code "62") (name "Net-(U2-PC11{slash}USART4_RX{slash}SDIO_D3)") (class "Default")
      (node (ref "PC") (pin "5") (pinfunction "5_5") (pintype "passive"))
      (node (ref "U2") (pin "112") (pinfunction "PC11/USART4_RX/SDIO_D3_112") (pintype "passive"))
    )
    (net (code "63") (name "Net-(U2-PC12{slash}USART5_TX{slash}SDIO_CK)") (class "Default")
      (node (ref "PC") (pin "4") (pinfunction "4_4") (pintype "passive"))
      (node (ref "U2") (pin "113") (pinfunction "PC12/USART5_TX/SDIO_CK_113") (pintype "passive"))
    )
    (net (code "64") (name "Net-(U2-PC13-TAMPER-RTC)") (class "Default")
      (node (ref "PC") (pin "3") (pinfunction "3_3") (pintype "passive"))
      (node (ref "U2") (pin "7") (pinfunction "PC13-TAMPER-RTC_7") (pintype "passive"))
    )
    (net (code "65") (name "Net-(U2-PC14-OSC32_IN)") (class "Default")
      (node (ref "PC") (pin "2") (pinfunction "2_2") (pintype "passive"))
      (node (ref "U2") (pin "8") (pinfunction "PC14-OSC32_IN_8") (pintype "passive"))
    )
    (net (code "66") (name "Net-(U2-PC15-OSC32_OUT)") (class "Default")
      (node (ref "PC") (pin "1") (pinfunction "1_1") (pintype "passive"))
      (node (ref "U2") (pin "9") (pinfunction "PC15-OSC32_OUT_9") (pintype "passive"))
    )
    (net (code "67") (name "Net-(U2-PD0{slash}FSMC_D2)") (class "Default")
      (node (ref "PD") (pin "16") (pinfunction "16_16") (pintype "passive"))
      (node (ref "U2") (pin "114") (pinfunction "PD0/FSMC_D2_114") (pintype "passive"))
    )
    (net (code "68") (name "Net-(U2-PD1{slash}FSMC_D3)") (class "Default")
      (node (ref "PD") (pin "15") (pinfunction "15_15") (pintype "passive"))
      (node (ref "U2") (pin "115") (pinfunction "PD1/FSMC_D3_115") (pintype "passive"))
    )
    (net (code "69") (name "Net-(U2-PD2{slash}TIM3_ETR{slash}USART5_RX{slash}SDIO_CMD)") (class "Default")
      (node (ref "PD") (pin "14") (pinfunction "14_14") (pintype "passive"))
      (node (ref "U2") (pin "116") (pinfunction "PD2/TIM3_ETR/USART5_RX/SDIO_CMD_116") (pintype "passive"))
    )
    (net (code "70") (name "Net-(U2-PD3{slash}FSMC_CLK)") (class "Default")
      (node (ref "PD") (pin "13") (pinfunction "13_13") (pintype "passive"))
      (node (ref "U2") (pin "117") (pinfunction "PD3/FSMC_CLK_117") (pintype "passive"))
    )
    (net (code "71") (name "Net-(U2-PD4{slash}FSMC_NOE)") (class "Default")
      (node (ref "PD") (pin "12") (pinfunction "12_12") (pintype "passive"))
      (node (ref "U2") (pin "118") (pinfunction "PD4/FSMC_NOE_118") (pintype "passive"))
    )
    (net (code "72") (name "Net-(U2-PD5{slash}FSMC_NWE)") (class "Default")
      (node (ref "PD") (pin "11") (pinfunction "11_11") (pintype "passive"))
      (node (ref "U2") (pin "119") (pinfunction "PD5/FSMC_NWE_119") (pintype "passive"))
    )
    (net (code "73") (name "Net-(U2-PD6{slash}FSMC_NWAIT)") (class "Default")
      (node (ref "PD") (pin "10") (pinfunction "10_10") (pintype "passive"))
      (node (ref "U2") (pin "122") (pinfunction "PD6/FSMC_NWAIT_122") (pintype "passive"))
    )
    (net (code "74") (name "Net-(U2-PD7{slash}FSMC_NE1{slash}FSMC_NCE2)") (class "Default")
      (node (ref "PD") (pin "9") (pinfunction "9_9") (pintype "passive"))
      (node (ref "U2") (pin "123") (pinfunction "PD7/FSMC_NE1/FSMC_NCE2_123") (pintype "passive"))
    )
    (net (code "75") (name "Net-(U2-PD8{slash}FSMC_D13)") (class "Default")
      (node (ref "PD") (pin "8") (pinfunction "8_8") (pintype "passive"))
      (node (ref "U2") (pin "77") (pinfunction "PD8/FSMC_D13_77") (pintype "passive"))
    )
    (net (code "76") (name "Net-(U2-PD9{slash}FSMC_D14)") (class "Default")
      (node (ref "PD") (pin "7") (pinfunction "7_7") (pintype "passive"))
      (node (ref "U2") (pin "78") (pinfunction "PD9/FSMC_D14_78") (pintype "passive"))
    )
    (net (code "77") (name "Net-(U2-PD10{slash}FSMC_D15)") (class "Default")
      (node (ref "PD") (pin "6") (pinfunction "6_6") (pintype "passive"))
      (node (ref "U2") (pin "79") (pinfunction "PD10/FSMC_D15_79") (pintype "passive"))
    )
    (net (code "78") (name "Net-(U2-PD11{slash}FSMC_A16)") (class "Default")
      (node (ref "PD") (pin "5") (pinfunction "5_5") (pintype "passive"))
      (node (ref "U2") (pin "80") (pinfunction "PD11/FSMC_A16_80") (pintype "passive"))
    )
    (net (code "79") (name "Net-(U2-PD12{slash}FSMC_A17)") (class "Default")
      (node (ref "PD") (pin "4") (pinfunction "4_4") (pintype "passive"))
      (node (ref "U2") (pin "81") (pinfunction "PD12/FSMC_A17_81") (pintype "passive"))
    )
    (net (code "80") (name "Net-(U2-PD13{slash}FSMC_A18)") (class "Default")
      (node (ref "PD") (pin "3") (pinfunction "3_3") (pintype "passive"))
      (node (ref "U2") (pin "82") (pinfunction "PD13/FSMC_A18_82") (pintype "passive"))
    )
    (net (code "81") (name "Net-(U2-PD14{slash}FSMC_D0)") (class "Default")
      (node (ref "PD") (pin "2") (pinfunction "2_2") (pintype "passive"))
      (node (ref "U2") (pin "85") (pinfunction "PD14/FSMC_D0_85") (pintype "passive"))
    )
    (net (code "82") (name "Net-(U2-PD15{slash}FSMC_D1)") (class "Default")
      (node (ref "PD") (pin "1") (pinfunction "1_1") (pintype "passive"))
      (node (ref "U2") (pin "86") (pinfunction "PD15/FSMC_D1_86") (pintype "passive"))
    )
    (net (code "83") (name "Net-(U2-PE0{slash}TIM4_ETR{slash}FSMC_NBL0)") (class "Default")
      (node (ref "PE") (pin "1") (pinfunction "1_1") (pintype "passive"))
      (node (ref "U2") (pin "141") (pinfunction "PE0/TIM4_ETR/FSMC_NBL0_141") (pintype "passive"))
    )
    (net (code "84") (name "Net-(U2-PE1{slash}FSMC_NBL1)") (class "Default")
      (node (ref "PE") (pin "2") (pinfunction "2_2") (pintype "passive"))
      (node (ref "U2") (pin "142") (pinfunction "PE1/FSMC_NBL1_142") (pintype "passive"))
    )
    (net (code "85") (name "Net-(U2-PE2{slash}TRACECK{slash}FSMC_A23)") (class "Default")
      (node (ref "PE") (pin "3") (pinfunction "3_3") (pintype "passive"))
      (node (ref "U2") (pin "1") (pinfunction "PE2/TRACECK/FSMC_A23_1") (pintype "passive"))
    )
    (net (code "86") (name "Net-(U2-PE3{slash}TRACED0{slash}FSMC_A19)") (class "Default")
      (node (ref "PE") (pin "4") (pinfunction "4_4") (pintype "passive"))
      (node (ref "U2") (pin "2") (pinfunction "PE3/TRACED0/FSMC_A19_2") (pintype "passive"))
    )
    (net (code "87") (name "Net-(U2-PE4{slash}TRACED1{slash}FSMC_A20)") (class "Default")
      (node (ref "PE") (pin "5") (pinfunction "5_5") (pintype "passive"))
      (node (ref "U2") (pin "3") (pinfunction "PE4/TRACED1/FSMC_A20_3") (pintype "passive"))
    )
    (net (code "88") (name "Net-(U2-PE5{slash}TRACED2{slash}FSMC_A21)") (class "Default")
      (node (ref "PE") (pin "6") (pinfunction "6_6") (pintype "passive"))
      (node (ref "U2") (pin "4") (pinfunction "PE5/TRACED2/FSMC_A21_4") (pintype "passive"))
    )
    (net (code "89") (name "Net-(U2-PE6{slash}TRACED3{slash}FSMC_A22)") (class "Default")
      (node (ref "PE") (pin "7") (pinfunction "7_7") (pintype "passive"))
      (node (ref "U2") (pin "5") (pinfunction "PE6/TRACED3/FSMC_A22_5") (pintype "passive"))
    )
    (net (code "90") (name "Net-(U2-PE7{slash}FSMC_D4)") (class "Default")
      (node (ref "PE") (pin "8") (pinfunction "8_8") (pintype "passive"))
      (node (ref "U2") (pin "58") (pinfunction "PE7/FSMC_D4_58") (pintype "passive"))
    )
    (net (code "91") (name "Net-(U2-PE8{slash}FSMC_D5)") (class "Default")
      (node (ref "PE") (pin "9") (pinfunction "9_9") (pintype "passive"))
      (node (ref "U2") (pin "59") (pinfunction "PE8/FSMC_D5_59") (pintype "passive"))
    )
    (net (code "92") (name "Net-(U2-PE9{slash}FSMC_D6)") (class "Default")
      (node (ref "PE") (pin "10") (pinfunction "10_10") (pintype "passive"))
      (node (ref "U2") (pin "60") (pinfunction "PE9/FSMC_D6_60") (pintype "passive"))
    )
    (net (code "93") (name "Net-(U2-PE10{slash}FSMC_D7)") (class "Default")
      (node (ref "PE") (pin "11") (pinfunction "11_11") (pintype "passive"))
      (node (ref "U2") (pin "63") (pinfunction "PE10/FSMC_D7_63") (pintype "passive"))
    )
    (net (code "94") (name "Net-(U2-PE11{slash}FSMC_D8)") (class "Default")
      (node (ref "PE") (pin "12") (pinfunction "12_12") (pintype "passive"))
      (node (ref "U2") (pin "64") (pinfunction "PE11/FSMC_D8_64") (pintype "passive"))
    )
    (net (code "95") (name "Net-(U2-PE12{slash}FSMC_D9)") (class "Default")
      (node (ref "PE") (pin "13") (pinfunction "13_13") (pintype "passive"))
      (node (ref "U2") (pin "65") (pinfunction "PE12/FSMC_D9_65") (pintype "passive"))
    )
    (net (code "96") (name "Net-(U2-PE13{slash}FSMC_D10)") (class "Default")
      (node (ref "PE") (pin "14") (pinfunction "14_14") (pintype "passive"))
      (node (ref "U2") (pin "66") (pinfunction "PE13/FSMC_D10_66") (pintype "passive"))
    )
    (net (code "97") (name "Net-(U2-PE14{slash}FSMC_D11)") (class "Default")
      (node (ref "PE") (pin "15") (pinfunction "15_15") (pintype "passive"))
      (node (ref "U2") (pin "67") (pinfunction "PE14/FSMC_D11_67") (pintype "passive"))
    )
    (net (code "98") (name "Net-(U2-PE15{slash}FSMC_D12)") (class "Default")
      (node (ref "PE") (pin "16") (pinfunction "16_16") (pintype "passive"))
      (node (ref "U2") (pin "68") (pinfunction "PE15/FSMC_D12_68") (pintype "passive"))
    )
    (net (code "99") (name "Net-(U2-PF0{slash}FSMC_A0)") (class "Default")
      (node (ref "PF") (pin "1") (pinfunction "1_1") (pintype "passive"))
      (node (ref "U2") (pin "10") (pinfunction "PF0/FSMC_A0_10") (pintype "passive"))
    )
    (net (code "100") (name "Net-(U2-PF1{slash}FSMC_A1)") (class "Default")
      (node (ref "PF") (pin "2") (pinfunction "2_2") (pintype "passive"))
      (node (ref "U2") (pin "11") (pinfunction "PF1/FSMC_A1_11") (pintype "passive"))
    )
    (net (code "101") (name "Net-(U2-PF2{slash}FSMC_A2)") (class "Default")
      (node (ref "PF") (pin "3") (pinfunction "3_3") (pintype "passive"))
      (node (ref "U2") (pin "12") (pinfunction "PF2/FSMC_A2_12") (pintype "passive"))
    )
    (net (code "102") (name "Net-(U2-PF3{slash}FSMC_A3)") (class "Default")
      (node (ref "PF") (pin "4") (pinfunction "4_4") (pintype "passive"))
      (node (ref "U2") (pin "13") (pinfunction "PF3/FSMC_A3_13") (pintype "passive"))
    )
    (net (code "103") (name "Net-(U2-PF4{slash}FSMC_A4)") (class "Default")
      (node (ref "PF") (pin "5") (pinfunction "5_5") (pintype "passive"))
      (node (ref "U2") (pin "14") (pinfunction "PF4/FSMC_A4_14") (pintype "passive"))
    )
    (net (code "104") (name "Net-(U2-PF5{slash}FSMC_A5)") (class "Default")
      (node (ref "PF") (pin "6") (pinfunction "6_6") (pintype "passive"))
      (node (ref "U2") (pin "15") (pinfunction "PF5/FSMC_A5_15") (pintype "passive"))
    )
    (net (code "105") (name "Net-(U2-PF6{slash}ADC3_IN4{slash}FSMC_NIORD)") (class "Default")
      (node (ref "PF") (pin "7") (pinfunction "7_7") (pintype "passive"))
      (node (ref "U2") (pin "18") (pinfunction "PF6/ADC3_IN4/FSMC_NIORD_18") (pintype "passive"))
    )
    (net (code "106") (name "Net-(U2-PF7{slash}ADC3_IN5{slash}FSMC_NREG)") (class "Default")
      (node (ref "PF") (pin "8") (pinfunction "8_8") (pintype "passive"))
      (node (ref "U2") (pin "19") (pinfunction "PF7/ADC3_IN5/FSMC_NREG_19") (pintype "passive"))
    )
    (net (code "107") (name "Net-(U2-PF8{slash}ADC3_IN6{slash}FSMC_NIOWR)") (class "Default")
      (node (ref "PF") (pin "9") (pinfunction "9_9") (pintype "passive"))
      (node (ref "U2") (pin "20") (pinfunction "PF8/ADC3_IN6/FSMC_NIOWR_20") (pintype "passive"))
    )
    (net (code "108") (name "Net-(U2-PF9{slash}ADC3_IN7{slash}FSMC_CD)") (class "Default")
      (node (ref "PF") (pin "10") (pinfunction "10_10") (pintype "passive"))
      (node (ref "U2") (pin "21") (pinfunction "PF9/ADC3_IN7/FSMC_CD_21") (pintype "passive"))
    )
    (net (code "109") (name "Net-(U2-PF10{slash}ADC3_IN8{slash}FSMC_INTR)") (class "Default")
      (node (ref "PF") (pin "11") (pinfunction "11_11") (pintype "passive"))
      (node (ref "U2") (pin "22") (pinfunction "PF10/ADC3_IN8/FSMC_INTR_22") (pintype "passive"))
    )
    (net (code "110") (name "Net-(U2-PF11{slash}FSMC_NIOS16)") (class "Default")
      (node (ref "PF") (pin "12") (pinfunction "12_12") (pintype "passive"))
      (node (ref "U2") (pin "49") (pinfunction "PF11/FSMC_NIOS16_49") (pintype "passive"))
    )
    (net (code "111") (name "Net-(U2-PF12{slash}FSMC_A6)") (class "Default")
      (node (ref "PF") (pin "13") (pinfunction "13_13") (pintype "passive"))
      (node (ref "U2") (pin "50") (pinfunction "PF12/FSMC_A6_50") (pintype "passive"))
    )
    (net (code "112") (name "Net-(U2-PF13{slash}FSMC_A7)") (class "Default")
      (node (ref "PF") (pin "14") (pinfunction "14_14") (pintype "passive"))
      (node (ref "U2") (pin "53") (pinfunction "PF13/FSMC_A7_53") (pintype "passive"))
    )
    (net (code "113") (name "Net-(U2-PF14{slash}FSMC_A8)") (class "Default")
      (node (ref "PF") (pin "15") (pinfunction "15_15") (pintype "passive"))
      (node (ref "U2") (pin "54") (pinfunction "PF14/FSMC_A8_54") (pintype "passive"))
    )
    (net (code "114") (name "Net-(U2-PF15{slash}FSMC_A9)") (class "Default")
      (node (ref "PF") (pin "16") (pinfunction "16_16") (pintype "passive"))
      (node (ref "U2") (pin "55") (pinfunction "PF15/FSMC_A9_55") (pintype "passive"))
    )
    (net (code "115") (name "Net-(U2-PG0{slash}FSMC_A10)") (class "Default")
      (node (ref "PG") (pin "1") (pinfunction "1_1") (pintype "passive"))
      (node (ref "U2") (pin "56") (pinfunction "PG0/FSMC_A10_56") (pintype "passive"))
    )
    (net (code "116") (name "Net-(U2-PG1{slash}FSMC_A11)") (class "Default")
      (node (ref "PG") (pin "2") (pinfunction "2_2") (pintype "passive"))
      (node (ref "U2") (pin "57") (pinfunction "PG1/FSMC_A11_57") (pintype "passive"))
    )
    (net (code "117") (name "Net-(U2-PG2{slash}FSMC_A12)") (class "Default")
      (node (ref "PG") (pin "3") (pinfunction "3_3") (pintype "passive"))
      (node (ref "U2") (pin "87") (pinfunction "PG2/FSMC_A12_87") (pintype "passive"))
    )
    (net (code "118") (name "Net-(U2-PG3{slash}FSMC_A13)") (class "Default")
      (node (ref "PG") (pin "4") (pinfunction "4_4") (pintype "passive"))
      (node (ref "U2") (pin "88") (pinfunction "PG3/FSMC_A13_88") (pintype "passive"))
    )
    (net (code "119") (name "Net-(U2-PG4{slash}FSMC_A14)") (class "Default")
      (node (ref "PG") (pin "5") (pinfunction "5_5") (pintype "passive"))
      (node (ref "U2") (pin "89") (pinfunction "PG4/FSMC_A14_89") (pintype "passive"))
    )
    (net (code "120") (name "Net-(U2-PG5{slash}FSMC_A15)") (class "Default")
      (node (ref "PG") (pin "6") (pinfunction "6_6") (pintype "passive"))
      (node (ref "U2") (pin "90") (pinfunction "PG5/FSMC_A15_90") (pintype "passive"))
    )
    (net (code "121") (name "Net-(U2-PG6{slash}FSMC_INT2)") (class "Default")
      (node (ref "PG") (pin "7") (pinfunction "7_7") (pintype "passive"))
      (node (ref "U2") (pin "91") (pinfunction "PG6/FSMC_INT2_91") (pintype "passive"))
    )
    (net (code "122") (name "Net-(U2-PG7{slash}FSMC_INT3)") (class "Default")
      (node (ref "PG") (pin "8") (pinfunction "8_8") (pintype "passive"))
      (node (ref "U2") (pin "92") (pinfunction "PG7/FSMC_INT3_92") (pintype "passive"))
    )
    (net (code "123") (name "Net-(U2-PG8)") (class "Default")
      (node (ref "PG") (pin "9") (pinfunction "9_9") (pintype "passive"))
      (node (ref "U2") (pin "93") (pinfunction "PG8_93") (pintype "passive"))
    )
    (net (code "124") (name "Net-(U2-PG9{slash}FSMC_NE2{slash}FSMC_NCE3)") (class "Default")
      (node (ref "PG") (pin "10") (pinfunction "10_10") (pintype "passive"))
      (node (ref "U2") (pin "124") (pinfunction "PG9/FSMC_NE2/FSMC_NCE3_124") (pintype "passive"))
    )
    (net (code "125") (name "Net-(U2-PG10{slash}FSMC_NCE4_1{slash}FSMC_NE3)") (class "Default")
      (node (ref "PG") (pin "11") (pinfunction "11_11") (pintype "passive"))
      (node (ref "U2") (pin "125") (pinfunction "PG10/FSMC_NCE4_1/FSMC_NE3_125") (pintype "passive"))
    )
    (net (code "126") (name "Net-(U2-PG11{slash}FSMC_NCE4_2)") (class "Default")
      (node (ref "PG") (pin "12") (pinfunction "12_12") (pintype "passive"))
      (node (ref "U2") (pin "126") (pinfunction "PG11/FSMC_NCE4_2_126") (pintype "passive"))
    )
    (net (code "127") (name "Net-(U2-PG12{slash}FSMC_NE4)") (class "Default")
      (node (ref "PG") (pin "13") (pinfunction "13_13") (pintype "passive"))
      (node (ref "U2") (pin "127") (pinfunction "PG12/FSMC_NE4_127") (pintype "passive"))
    )
    (net (code "128") (name "Net-(U2-PG13{slash}FSMC_A24)") (class "Default")
      (node (ref "PG") (pin "14") (pinfunction "14_14") (pintype "passive"))
      (node (ref "U2") (pin "128") (pinfunction "PG13/FSMC_A24_128") (pintype "passive"))
    )
    (net (code "129") (name "Net-(U2-PG14{slash}FSMC_A25)") (class "Default")
      (node (ref "PG") (pin "15") (pinfunction "15_15") (pintype "passive"))
      (node (ref "U2") (pin "129") (pinfunction "PG14/FSMC_A25_129") (pintype "passive"))
    )
    (net (code "130") (name "Net-(U2-PG15)") (class "Default")
      (node (ref "PG") (pin "16") (pinfunction "16_16") (pintype "passive"))
      (node (ref "U2") (pin "132") (pinfunction "PG15_132") (pintype "passive"))
    )
    (net (code "131") (name "VCC") (class "Default")
      (node (ref "5V") (pin "1") (pinfunction "1_1") (pintype "passive"))
      (node (ref "5V") (pin "10") (pinfunction "10_10") (pintype "passive"))
      (node (ref "5V") (pin "2") (pinfunction "2_2") (pintype "passive"))
      (node (ref "5V") (pin "3") (pinfunction "3_3") (pintype "passive"))
      (node (ref "5V") (pin "4") (pinfunction "4_4") (pintype "passive"))
      (node (ref "5V") (pin "5") (pinfunction "5_5") (pintype "passive"))
      (node (ref "5V") (pin "6") (pinfunction "6_6") (pintype "passive"))
      (node (ref "5V") (pin "7") (pinfunction "7_7") (pintype "passive"))
      (node (ref "5V") (pin "8") (pinfunction "8_8") (pintype "passive"))
      (node (ref "5V") (pin "9") (pinfunction "9_9") (pintype "passive"))
      (node (ref "CH1") (pin "16") (pinfunction "VCC_16") (pintype "passive"))
      (node (ref "J1") (pin "1") (pinfunction "VCC_1") (pintype "passive"))
      (node (ref "U5") (pin "3") (pinfunction "IN_3") (pintype "passive"))
    )
    (net (code "132") (name "unconnected-(CH1-CTS#-Pad9)") (class "Default")
      (node (ref "CH1") (pin "9") (pinfunction "CTS#_9") (pintype "passive"))
    )
    (net (code "133") (name "unconnected-(CH1-DCD#-Pad12)") (class "Default")
      (node (ref "CH1") (pin "12") (pinfunction "DCD#_12") (pintype "passive"))
    )
    (net (code "134") (name "unconnected-(CH1-DSR#-Pad10)") (class "Default")
      (node (ref "CH1") (pin "10") (pinfunction "DSR#_10") (pintype "passive"))
    )
    (net (code "135") (name "unconnected-(CH1-R232-Pad15)") (class "Default")
      (node (ref "CH1") (pin "15") (pinfunction "R232_15") (pintype "passive"))
    )
    (net (code "136") (name "unconnected-(CH1-RI#-Pad11)") (class "Default")
      (node (ref "CH1") (pin "11") (pinfunction "RI#_11") (pintype "passive"))
    )
    (net (code "137") (name "unconnected-(J1-SHELL-Pad5)") (class "Default")
      (node (ref "J1") (pin "5") (pinfunction "SHELL_5") (pintype "passive+no_connect"))
    )
    (net (code "138") (name "unconnected-(J1-SHELL-Pad6)") (class "Default")
      (node (ref "J1") (pin "6") (pinfunction "SHELL_6") (pintype "passive+no_connect"))
    )
    (net (code "139") (name "unconnected-(U2-NC-Pad106)") (class "Default")
      (node (ref "U2") (pin "106") (pinfunction "NC_106") (pintype "passive+no_connect"))
    )
  )
)
